# 05_POWER_SAMA7_Doc.net
KiCad netlist of a schematic drawn in Altium Designer
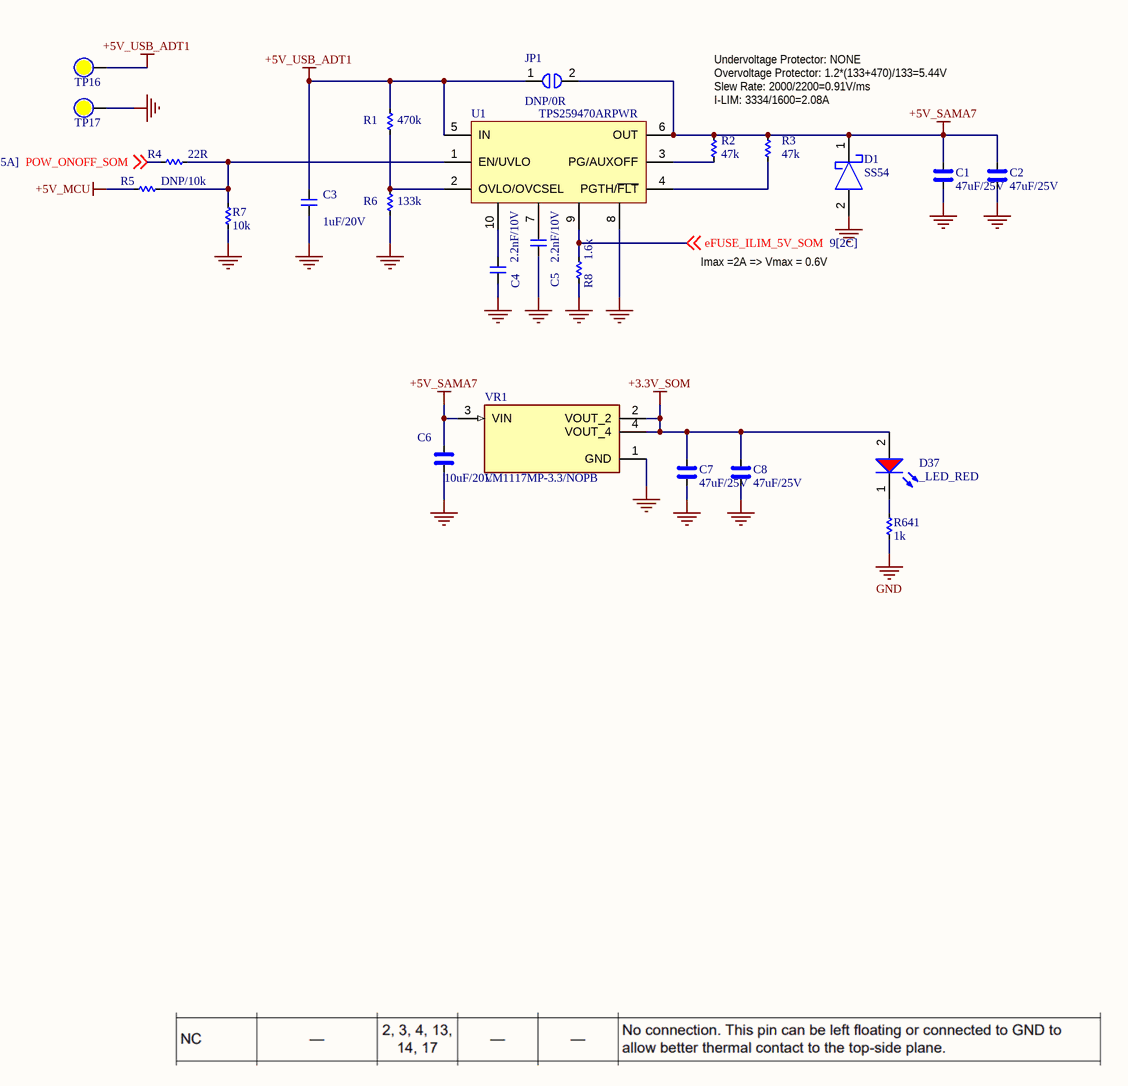
[diagram p0: 05_POWER_SAMA7.Doc.SchDoc]

(export (version "E")
  (design (tool "Eeschema 10.0.6"))
  (components
    (comp (ref "C1")
      (value "47uF/25V")
      (footprint "CAP_C_3225X80")
      (description "CAP CHIP High Value")
      (libsource (lib "LABLIB") (part "_CAP_C_High_2"))
    )
    (comp (ref "C2")
      (value "47uF/25V")
      (footprint "CAP_C_3225X80")
      (description "CAP CHIP High Value")
      (libsource (lib "LABLIB") (part "_CAP_C_High_2"))
    )
    (comp (ref "C3")
      (value "1uF/20V")
      (footprint "CAP_C_1005X60")
      (description "CAP CHIP")
      (libsource (lib "LABLIB") (part "_CAP_C_2"))
    )
    (comp (ref "C4")
      (value "2.2nF/10V")
      (footprint "CAP_C_1005X60")
      (description "CAP CHIP")
      (libsource (lib "LABLIB") (part "_CAP_C_2"))
    )
    (comp (ref "C5")
      (value "2.2nF/10V")
      (footprint "CAP_C_1005X60")
      (description "CAP CHIP")
      (libsource (lib "LABLIB") (part "_CAP_C_2"))
    )
    (comp (ref "C6")
      (value "10uF/20V")
      (footprint "CAP_C_2012X110")
      (description "CAP CHIP High Value")
      (libsource (lib "LABLIB") (part "_CAP_C_High_2"))
    )
    (comp (ref "C7")
      (value "47uF/25V")
      (footprint "CAP_C_3225X80")
      (description "CAP CHIP High Value")
      (libsource (lib "LABLIB") (part "_CAP_C_High_2"))
    )
    (comp (ref "C8")
      (value "47uF/25V")
      (footprint "CAP_C_3225X80")
      (description "CAP CHIP High Value")
      (libsource (lib "LABLIB") (part "_CAP_C_High_2"))
    )
    (comp (ref "D1")
      (value "SS54")
      (footprint "DO-214AC_SMA")
      (description "DIODE SCHOTTKY 60V 3A DO214AA")
      (libsource (lib "EXP_HW_V3") (part "SS54"))
    )
    (comp (ref "D37") (value "_LED_RED") (footprint "LED_0603") (libsource (lib "LABLIB") (part "_LED_RED")))
    (comp (ref "JP1")
      (value "DNP/0R")
      (footprint "RES_C_1608X60")
      (libsource (lib "LABLIB") (part "JUMPER_1_1"))
    )
    (comp (ref "R1")
      (value "470k")
      (footprint "RES_C_1005X40")
      (description "RES")
      (libsource (lib "LABLIB") (part "_RES_B_2"))
    )
    (comp (ref "R2")
      (value "47k")
      (footprint "RES_C_1005X40")
      (description "RES")
      (libsource (lib "LABLIB") (part "_RES_B_2"))
    )
    (comp (ref "R3")
      (value "47k")
      (footprint "RES_C_1005X40")
      (description "RES")
      (libsource (lib "LABLIB") (part "_RES_B_2"))
    )
    (comp (ref "R4")
      (value "22R")
      (footprint "RES_C_1005X40")
      (description "RES")
      (libsource (lib "LABLIB") (part "_RES_B_2"))
    )
    (comp (ref "R5")
      (value "DNP/10k")
      (footprint "RES_C_1005X40")
      (description "RES")
      (libsource (lib "LABLIB") (part "_RES_B_2"))
    )
    (comp (ref "R6")
      (value "133k")
      (footprint "RES_C_1005X40")
      (description "RES")
      (libsource (lib "LABLIB") (part "_RES_B_2"))
    )
    (comp (ref "R7")
      (value "10k")
      (footprint "RES_C_1005X40")
      (description "RES")
      (libsource (lib "LABLIB") (part "_RES_B_2"))
    )
    (comp (ref "R8")
      (value "1.6k")
      (footprint "RES_C_1005X40")
      (description "RES")
      (libsource (lib "LABLIB") (part "_RES_B_2"))
    )
    (comp (ref "R641")
      (value "1k")
      (footprint "RES_C_1005X40")
      (description "RES")
      (libsource (lib "LABLIB") (part "_RES_B_2"))
    )
    (comp (ref "TP16")
      (value "~")
      (footprint "Testpoint_TH_D130H80")
      (description "Test Point")
      (libsource (lib "LABLIB") (part "Test Point"))
    )
    (comp (ref "TP17")
      (value "~")
      (footprint "Testpoint_TH_D130H80")
      (description "Test Point")
      (libsource (lib "LABLIB") (part "Test Point"))
    )
    (comp (ref "U1")
      (value "TPS259470ARPWR")
      (footprint "VQFN-HR-10")
      (libsource (lib "EXP_HW_V3") (part "TPS259470ARPWR"))
    )
    (comp (ref "VR1")
      (value "LM1117MP-3.3/NOPB")
      (footprint "VREG_LM1117MP-3.3/NOPB")
      (description "800-mA 15-V linear voltage regulator")
      (fields (field (name "MF") "Texas Instruments"))
      (libsource (lib "new_component") (part "LM1117MP-3.3/NOPB"))
    )
  )
  (nets
    (net (code "1") (name "+3.3V_SOM") (class "Default")
      (node (ref "C7") (pin "2") (pinfunction "2_2") (pintype "passive"))
      (node (ref "C8") (pin "2") (pinfunction "2_2") (pintype "passive"))
      (node (ref "D37") (pin "2") (pinfunction "A_2") (pintype "passive"))
      (node (ref "VR1") (pin "2") (pinfunction "VOUT_2_2") (pintype "power_in"))
      (node (ref "VR1") (pin "4") (pinfunction "VOUT_4_4") (pintype "power_in"))
    )
    (net (code "2") (name "+5V_MCU") (class "Default")
      (node (ref "R5") (pin "2") (pinfunction "2_2") (pintype "passive"))
    )
    (net (code "3") (name "+5V_SAMA7") (class "Default")
      (node (ref "C1") (pin "2") (pinfunction "2_2") (pintype "passive"))
      (node (ref "C2") (pin "2") (pinfunction "2_2") (pintype "passive"))
      (node (ref "C6") (pin "1") (pinfunction "1_1") (pintype "passive"))
      (node (ref "D1") (pin "1") (pinfunction "1_1") (pintype "passive"))
      (node (ref "JP1") (pin "2") (pinfunction "2_2") (pintype "passive"))
      (node (ref "R2") (pin "2") (pinfunction "2_2") (pintype "passive"))
      (node (ref "R3") (pin "2") (pinfunction "2_2") (pintype "passive"))
      (node (ref "U1") (pin "6") (pinfunction "OUT_6") (pintype "passive"))
      (node (ref "VR1") (pin "3") (pinfunction "VIN_3") (pintype "input"))
    )
    (net (code "4") (name "+5V_USB_ADT1") (class "Default")
      (node (ref "C3") (pin "2") (pinfunction "2_2") (pintype "passive"))
      (node (ref "JP1") (pin "1") (pinfunction "1_1") (pintype "passive"))
      (node (ref "R1") (pin "2") (pinfunction "2_2") (pintype "passive"))
      (node (ref "TP16") (pin "1") (pinfunction "1_1") (pintype "passive"))
      (node (ref "U1") (pin "5") (pinfunction "IN_5") (pintype "passive"))
    )
    (net (code "5") (name "GND") (class "Default")
      (node (ref "C1") (pin "1") (pinfunction "1_1") (pintype "passive"))
      (node (ref "C2") (pin "1") (pinfunction "1_1") (pintype "passive"))
      (node (ref "C3") (pin "1") (pinfunction "1_1") (pintype "passive"))
      (node (ref "C4") (pin "1") (pinfunction "1_1") (pintype "passive"))
      (node (ref "C5") (pin "1") (pinfunction "1_1") (pintype "passive"))
      (node (ref "C6") (pin "2") (pinfunction "2_2") (pintype "passive"))
      (node (ref "C7") (pin "1") (pinfunction "1_1") (pintype "passive"))
      (node (ref "C8") (pin "1") (pinfunction "1_1") (pintype "passive"))
      (node (ref "D1") (pin "2") (pinfunction "2_2") (pintype "passive"))
      (node (ref "R6") (pin "1") (pinfunction "1_1") (pintype "passive"))
      (node (ref "R641") (pin "1") (pinfunction "1_1") (pintype "passive"))
      (node (ref "R7") (pin "2") (pinfunction "2_2") (pintype "passive"))
      (node (ref "R8") (pin "1") (pinfunction "1_1") (pintype "passive"))
      (node (ref "TP17") (pin "1") (pinfunction "1_1") (pintype "passive"))
      (node (ref "U1") (pin "8") (pinfunction "8_8") (pintype "passive"))
      (node (ref "VR1") (pin "1") (pinfunction "GND_1") (pintype "power_in"))
    )
    (net (code "6") (name "Net-(C4-Pad2)") (class "Default")
      (node (ref "C4") (pin "2") (pinfunction "2_2") (pintype "passive"))
      (node (ref "U1") (pin "10") (pinfunction "10_10") (pintype "passive"))
    )
    (net (code "7") (name "Net-(C5-Pad2)") (class "Default")
      (node (ref "C5") (pin "2") (pinfunction "2_2") (pintype "passive"))
      (node (ref "U1") (pin "7") (pinfunction "7_7") (pintype "passive"))
    )
    (net (code "8") (name "Net-(D37-K)") (class "Default")
      (node (ref "D37") (pin "1") (pinfunction "K_1") (pintype "passive"))
      (node (ref "R641") (pin "2") (pinfunction "2_2") (pintype "passive"))
    )
    (net (code "9") (name "Net-(U1-EN{slash}UVLO)") (class "Default")
      (node (ref "R4") (pin "1") (pinfunction "1_1") (pintype "passive"))
      (node (ref "R5") (pin "1") (pinfunction "1_1") (pintype "passive"))
      (node (ref "R7") (pin "1") (pinfunction "1_1") (pintype "passive"))
      (node (ref "U1") (pin "1") (pinfunction "EN/UVLO_1") (pintype "passive"))
    )
    (net (code "10") (name "Net-(U1-OVLO{slash}OVCSEL)") (class "Default")
      (node (ref "R1") (pin "1") (pinfunction "1_1") (pintype "passive"))
      (node (ref "R6") (pin "2") (pinfunction "2_2") (pintype "passive"))
      (node (ref "U1") (pin "2") (pinfunction "OVLO/OVCSEL_2") (pintype "passive"))
    )
    (net (code "11") (name "Net-(U1-PGTH{slash}~{FLT})") (class "Default")
      (node (ref "R3") (pin "1") (pinfunction "1_1") (pintype "passive"))
      (node (ref "U1") (pin "4") (pinfunction "PGTH/~{FLT}_4") (pintype "passive"))
    )
    (net (code "12") (name "Net-(U1-PG{slash}AUXOFF)") (class "Default")
      (node (ref "R2") (pin "1") (pinfunction "1_1") (pintype "passive"))
      (node (ref "U1") (pin "3") (pinfunction "PG/AUXOFF_3") (pintype "passive"))
    )
    (net (code "13") (name "POW_ONOFF_SOM") (class "Default")
      (node (ref "R4") (pin "2") (pinfunction "2_2") (pintype "passive"))
    )
    (net (code "14") (name "eFUSE_ILIM_5V_SOM") (class "Default")
      (node (ref "R8") (pin "2") (pinfunction "2_2") (pintype "passive"))
      (node (ref "U1") (pin "9") (pinfunction "9_9") (pintype "passive"))
    )
  )
)
